# business_card.net
KiCad netlist of a schematic drawn in Altium Designer
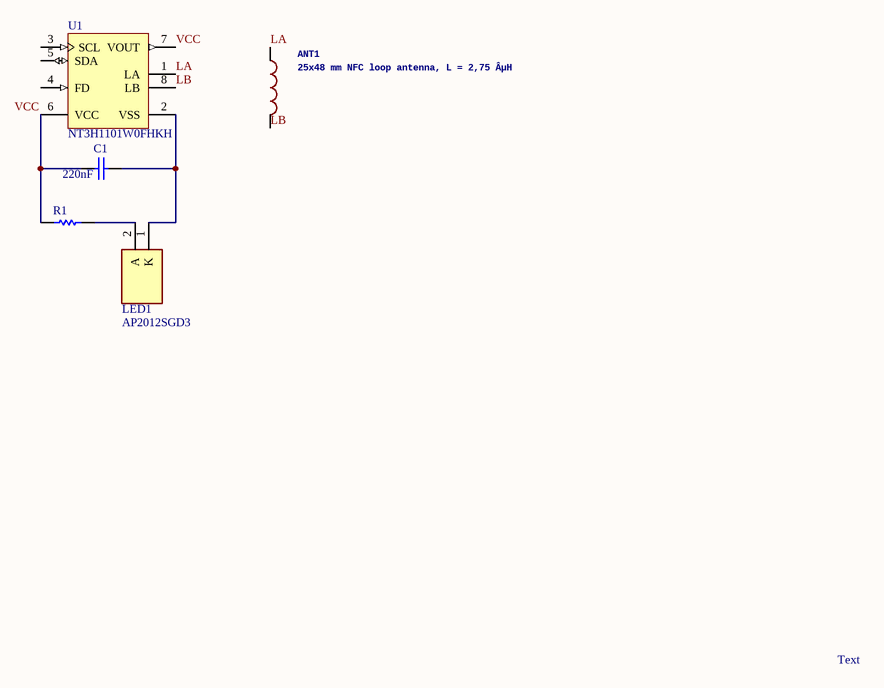
[diagram p0: business card.SchDoc]

(export (version "E")
  (design (tool "Eeschema 10.0.6"))
  (components
    (comp (ref "ANT1")
      (value "25x48 mm NFC loop antenna, L = 2,75 ÂµH")
      (footprint "25X48MM_NFC_ANTENNA")
      (libsource (lib "PCB_BusinessCard") (part "25X48MM_NFC_ANTENNA"))
    )
    (comp (ref "C1")
      (value "220nF")
      (footprint "CAPC1608X90X35ML10T15")
      (fields (field (name "PART NUMBER") "GRM188R70J224KA88D") (field (name "MANUFACTURER") "Murata"))
      (libsource (lib "Altium Content Vault") (part "CAP"))
    )
    (comp (ref "LED1")
      (value "AP2012SGD3")
      (footprint "SamacSys:LEDC2012X110N")
      (description "LED")
      (fields (field (name "MOUSER2 PART NUMBER") "604-AP2012SGD3"))
      (libsource (lib "*") (part "AP2012SGD3"))
    )
    (comp (ref "R1")
      (value "ERJ-6ENF4700V")
      (footprint "RESC2013X70X40ML20T20")
      (description "Chip Resistor, 470 Ohm, +/- 1%, 0.125 W, -55 to 155 degC, 0805 (2012 Metric), RoHS, Tape and Reel")
      (libsource (lib "Altium Content Vault") (part "RES-2"))
    )
    (comp (ref "U1")
      (value "NT3H1101W0FHKH")
      (footprint "NXP-SOT902-3_V")
      (fields (field (name "MANUFACTURER") "NXP"))
      (libsource (lib "Altium Content Vault") (part "NXP-NT3H1101-SOT902-3-8"))
    )
  )
  (nets
    (net (code "1") (name "/LA") (class "Default")
      (node (ref "ANT1") (pin "P$1") (pinfunction "P$1_P$1") (pintype "passive"))
      (node (ref "U1") (pin "1") (pinfunction "LA_1") (pintype "passive"))
    )
    (net (code "2") (name "/LB") (class "Default")
      (node (ref "ANT1") (pin "P$2") (pinfunction "P$2_P$2") (pintype "passive"))
      (node (ref "U1") (pin "8") (pinfunction "LB_8") (pintype "passive"))
    )
    (net (code "3") (name "/VCC") (class "Default")
      (node (ref "C1") (pin "1") (pinfunction "1_1") (pintype "passive"))
      (node (ref "R1") (pin "1") (pinfunction "1_1") (pintype "passive"))
      (node (ref "U1") (pin "6") (pinfunction "VCC_6") (pintype "power_in"))
      (node (ref "U1") (pin "7") (pinfunction "VOUT_7") (pintype "output"))
    )
    (net (code "4") (name "Net-(LED1-A)") (class "Default")
      (node (ref "LED1") (pin "2") (pinfunction "A_2") (pintype "passive"))
      (node (ref "R1") (pin "2") (pinfunction "2_2") (pintype "passive"))
    )
    (net (code "5") (name "Net-(LED1-K)") (class "Default")
      (node (ref "C1") (pin "2") (pinfunction "2_2") (pintype "passive"))
      (node (ref "LED1") (pin "1") (pinfunction "K_1") (pintype "passive"))
      (node (ref "U1") (pin "2") (pinfunction "VSS_2") (pintype "power_in"))
    )
    (net (code "6") (name "unconnected-(U1-FD-Pad4)") (class "Default")
      (node (ref "U1") (pin "4") (pinfunction "FD_4") (pintype "input"))
    )
    (net (code "7") (name "unconnected-(U1-SCL-Pad3)") (class "Default")
      (node (ref "U1") (pin "3") (pinfunction "SCL_3") (pintype "input"))
    )
    (net (code "8") (name "unconnected-(U1-SDA-Pad5)") (class "Default")
      (node (ref "U1") (pin "5") (pinfunction "SDA_5") (pintype "bidirectional"))
    )
  )
)
